# another_one.net
KiCad netlist of a schematic drawn in EAGLE
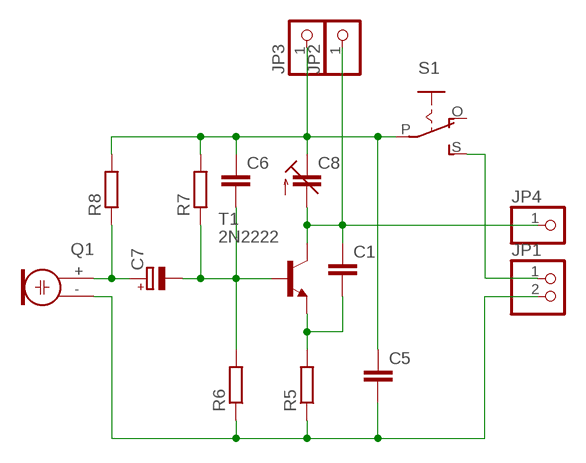
[diagram p0: schematic, sheet 1]

(export (version "E")
  (design (tool "Eeschema 10.0.6"))
  (components
    (comp (ref "C1")
      (value "C-EU025-025X050")
      (footprint "eagle-import:C025-025X050")
      (libsource (lib "eagle-import") (part "C-EU025-025X050"))
    )
    (comp (ref "C5")
      (value "C-EU025-025X050")
      (footprint "eagle-import:C025-025X050")
      (libsource (lib "eagle-import") (part "C-EU025-025X050"))
    )
    (comp (ref "C6")
      (value "C-EU025-025X050")
      (footprint "eagle-import:C025-025X050")
      (libsource (lib "eagle-import") (part "C-EU025-025X050"))
    )
    (comp (ref "C7")
      (value "CPOL-EUE2,5-6E")
      (footprint "eagle-import:E2,5-6E")
      (libsource (lib "eagle-import") (part "CPOL-EUE2,5-6E"))
    )
    (comp (ref "C8")
      (value "C-TRIMM808")
      (footprint "eagle-import:CTRIM808-BC")
      (libsource (lib "eagle-import") (part "C-TRIMM808"))
    )
    (comp (ref "JP1")
      (value "PINHD-1X2")
      (footprint "eagle-import:1X02")
      (libsource (lib "eagle-import") (part "PINHD-1X2"))
    )
    (comp (ref "JP2")
      (value "PINHD-1X1CB")
      (footprint "eagle-import:1X01-CLEANBIG")
      (libsource (lib "eagle-import") (part "PINHD-1X1CB"))
    )
    (comp (ref "JP3")
      (value "PINHD-1X1CB")
      (footprint "eagle-import:1X01-CLEANBIG")
      (libsource (lib "eagle-import") (part "PINHD-1X1CB"))
    )
    (comp (ref "JP4")
      (value "PINHD-1X1CB")
      (footprint "eagle-import:1X01-CLEANBIG")
      (libsource (lib "eagle-import") (part "PINHD-1X1CB"))
    )
    (comp (ref "Q1")
      (value "ELECTRET")
      (footprint "eagle-import:9.7ELECTRET")
      (libsource (lib "eagle-import") (part "ELECTRET"))
    )
    (comp (ref "R5")
      (value "R-EU_0204/5")
      (footprint "eagle-import:0204_5")
      (libsource (lib "eagle-import") (part "R-EU_0204/5"))
    )
    (comp (ref "R6")
      (value "R-EU_0207/2V")
      (footprint "eagle-import:0207_2V")
      (libsource (lib "eagle-import") (part "R-EU_0207/2V"))
    )
    (comp (ref "R7")
      (value "R-EU_0207/2V")
      (footprint "eagle-import:0207_2V")
      (libsource (lib "eagle-import") (part "R-EU_0207/2V"))
    )
    (comp (ref "R8")
      (value "R-EU_0207/2V")
      (footprint "eagle-import:0207_2V")
      (libsource (lib "eagle-import") (part "R-EU_0207/2V"))
    )
    (comp (ref "S1")
      (value "EG1218S")
      (footprint "eagle-import:EG1218")
      (libsource (lib "eagle-import") (part "EG1218S"))
    )
    (comp (ref "T1")
      (value "2N2222")
      (footprint "eagle-import:TO92-EBC-OVAL")
      (libsource (lib "eagle-import") (part "2N2222"))
    )
  )
  (nets
    (net (code "1") (name "Net-(C1-Pad2)") (class "Default")
      (node (ref "C1") (pin "2") (pinfunction "2_2") (pintype "passive"))
      (node (ref "R5") (pin "2") (pinfunction "2_2") (pintype "passive"))
      (node (ref "T1") (pin "E") (pinfunction "E_E") (pintype "passive"))
    )
    (net (code "2") (name "Net-(C6-Pad2)") (class "Default")
      (node (ref "C6") (pin "2") (pinfunction "2_2") (pintype "passive"))
      (node (ref "C7") (pin "-") (pinfunction "-_-") (pintype "passive"))
      (node (ref "R6") (pin "2") (pinfunction "2_2") (pintype "passive"))
      (node (ref "R7") (pin "1") (pinfunction "1_1") (pintype "passive"))
      (node (ref "T1") (pin "B") (pinfunction "B_B") (pintype "passive"))
    )
    (net (code "3") (name "Net-(C8-A)") (class "Default")
      (node (ref "C1") (pin "1") (pinfunction "1_1") (pintype "passive"))
      (node (ref "C8") (pin "2") (pinfunction "A_2") (pintype "passive"))
      (node (ref "JP2") (pin "1") (pinfunction "1_1") (pintype "passive"))
      (node (ref "JP4") (pin "1") (pinfunction "1_1") (pintype "passive"))
      (node (ref "T1") (pin "C") (pinfunction "C_C") (pintype "passive"))
    )
    (net (code "4") (name "Net-(C8-E)") (class "Default")
      (node (ref "C5") (pin "1") (pinfunction "1_1") (pintype "passive"))
      (node (ref "C6") (pin "1") (pinfunction "1_1") (pintype "passive"))
      (node (ref "C8") (pin "1") (pinfunction "E_1") (pintype "passive"))
      (node (ref "JP3") (pin "1") (pinfunction "1_1") (pintype "passive"))
      (node (ref "R7") (pin "2") (pinfunction "2_2") (pintype "passive"))
      (node (ref "R8") (pin "2") (pinfunction "2_2") (pintype "passive"))
      (node (ref "S1") (pin "P") (pinfunction "P_P") (pintype "passive"))
    )
    (net (code "5") (name "Net-(JP1-Pad1)") (class "Default")
      (node (ref "JP1") (pin "1") (pinfunction "1_1") (pintype "passive"))
      (node (ref "S1") (pin "S") (pinfunction "S_S") (pintype "passive"))
    )
    (net (code "6") (name "Net-(Q1-1)") (class "Default")
      (node (ref "C5") (pin "2") (pinfunction "2_2") (pintype "passive"))
      (node (ref "JP1") (pin "2") (pinfunction "2_2") (pintype "passive"))
      (node (ref "Q1") (pin "-") (pinfunction "1_-") (pintype "passive"))
      (node (ref "R5") (pin "1") (pinfunction "1_1") (pintype "passive"))
      (node (ref "R6") (pin "1") (pinfunction "1_1") (pintype "passive"))
    )
    (net (code "7") (name "Net-(Q1-2)") (class "Default")
      (node (ref "C7") (pin "+") (pinfunction "+_+") (pintype "passive"))
      (node (ref "Q1") (pin "+") (pinfunction "2_+") (pintype "passive"))
      (node (ref "R8") (pin "1") (pinfunction "1_1") (pintype "passive"))
    )
    (net (code "8") (name "unconnected-(S1-PadO)") (class "Default")
      (node (ref "S1") (pin "O") (pinfunction "O_O") (pintype "passive"))
    )
  )
)
